# LedOrgan.net
KiCad netlist of a schematic drawn in EAGLE
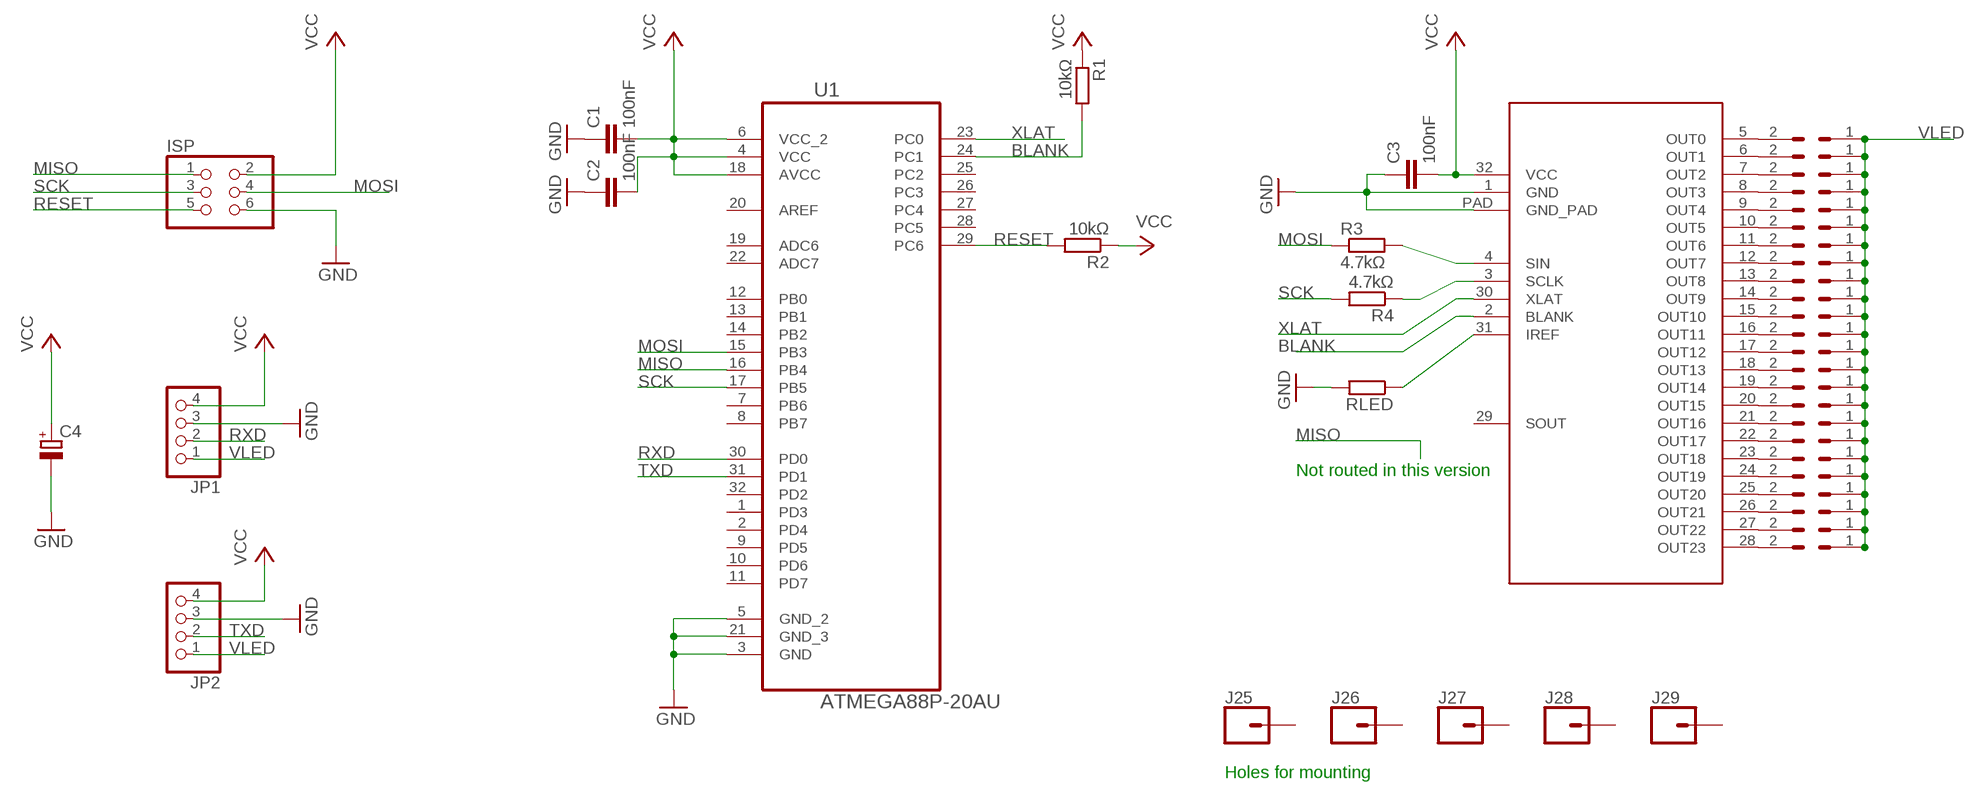
[diagram p0: schematic, sheet 1]

(export (version "E")
  (design (tool "Eeschema 10.0.6"))
  (components
    (comp (ref "C1")
      (value "100nF")
      (footprint "eagle-import:C0402")
      (libsource (lib "eagle-import") (part "C-EUC0402"))
    )
    (comp (ref "C2")
      (value "100nF")
      (footprint "eagle-import:C0402")
      (libsource (lib "eagle-import") (part "C-EUC0402"))
    )
    (comp (ref "C3")
      (value "100nF")
      (footprint "eagle-import:C0402")
      (libsource (lib "eagle-import") (part "C-EUC0402"))
    )
    (comp (ref "C4")
      (value "CPOL-EUE2.5-5")
      (footprint "eagle-import:E2,5-5")
      (libsource (lib "eagle-import") (part "CPOL-EUE2.5-5"))
    )
    (comp (ref "ISP")
      (value "PINHD-2X3")
      (footprint "eagle-import:2X03")
      (libsource (lib "eagle-import") (part "PINHD-2X3"))
    )
    (comp (ref "J1")
      (value "CONN_021X02_NO_SILK")
      (footprint "eagle-import:1X02_NO_SILK")
      (libsource (lib "eagle-import") (part "CONN_021X02_NO_SILK"))
    )
    (comp (ref "J2")
      (value "CONN_021X02_NO_SILK")
      (footprint "eagle-import:1X02_NO_SILK")
      (libsource (lib "eagle-import") (part "CONN_021X02_NO_SILK"))
    )
    (comp (ref "J3")
      (value "CONN_021X02_NO_SILK")
      (footprint "eagle-import:1X02_NO_SILK")
      (libsource (lib "eagle-import") (part "CONN_021X02_NO_SILK"))
    )
    (comp (ref "J4")
      (value "CONN_021X02_NO_SILK")
      (footprint "eagle-import:1X02_NO_SILK")
      (libsource (lib "eagle-import") (part "CONN_021X02_NO_SILK"))
    )
    (comp (ref "J5")
      (value "CONN_021X02_NO_SILK")
      (footprint "eagle-import:1X02_NO_SILK")
      (libsource (lib "eagle-import") (part "CONN_021X02_NO_SILK"))
    )
    (comp (ref "J6")
      (value "CONN_021X02_NO_SILK")
      (footprint "eagle-import:1X02_NO_SILK")
      (libsource (lib "eagle-import") (part "CONN_021X02_NO_SILK"))
    )
    (comp (ref "J7")
      (value "CONN_021X02_NO_SILK")
      (footprint "eagle-import:1X02_NO_SILK")
      (libsource (lib "eagle-import") (part "CONN_021X02_NO_SILK"))
    )
    (comp (ref "J8")
      (value "CONN_021X02_NO_SILK")
      (footprint "eagle-import:1X02_NO_SILK")
      (libsource (lib "eagle-import") (part "CONN_021X02_NO_SILK"))
    )
    (comp (ref "J9")
      (value "CONN_021X02_NO_SILK")
      (footprint "eagle-import:1X02_NO_SILK")
      (libsource (lib "eagle-import") (part "CONN_021X02_NO_SILK"))
    )
    (comp (ref "J10")
      (value "CONN_021X02_NO_SILK")
      (footprint "eagle-import:1X02_NO_SILK")
      (libsource (lib "eagle-import") (part "CONN_021X02_NO_SILK"))
    )
    (comp (ref "J11")
      (value "CONN_021X02_NO_SILK")
      (footprint "eagle-import:1X02_NO_SILK")
      (libsource (lib "eagle-import") (part "CONN_021X02_NO_SILK"))
    )
    (comp (ref "J12")
      (value "CONN_021X02_NO_SILK")
      (footprint "eagle-import:1X02_NO_SILK")
      (libsource (lib "eagle-import") (part "CONN_021X02_NO_SILK"))
    )
    (comp (ref "J13")
      (value "CONN_021X02_NO_SILK")
      (footprint "eagle-import:1X02_NO_SILK")
      (libsource (lib "eagle-import") (part "CONN_021X02_NO_SILK"))
    )
    (comp (ref "J14")
      (value "CONN_021X02_NO_SILK")
      (footprint "eagle-import:1X02_NO_SILK")
      (libsource (lib "eagle-import") (part "CONN_021X02_NO_SILK"))
    )
    (comp (ref "J15")
      (value "CONN_021X02_NO_SILK")
      (footprint "eagle-import:1X02_NO_SILK")
      (libsource (lib "eagle-import") (part "CONN_021X02_NO_SILK"))
    )
    (comp (ref "J16")
      (value "CONN_021X02_NO_SILK")
      (footprint "eagle-import:1X02_NO_SILK")
      (libsource (lib "eagle-import") (part "CONN_021X02_NO_SILK"))
    )
    (comp (ref "J17")
      (value "CONN_021X02_NO_SILK")
      (footprint "eagle-import:1X02_NO_SILK")
      (libsource (lib "eagle-import") (part "CONN_021X02_NO_SILK"))
    )
    (comp (ref "J18")
      (value "CONN_021X02_NO_SILK")
      (footprint "eagle-import:1X02_NO_SILK")
      (libsource (lib "eagle-import") (part "CONN_021X02_NO_SILK"))
    )
    (comp (ref "J19")
      (value "CONN_021X02_NO_SILK")
      (footprint "eagle-import:1X02_NO_SILK")
      (libsource (lib "eagle-import") (part "CONN_021X02_NO_SILK"))
    )
    (comp (ref "J20")
      (value "CONN_021X02_NO_SILK")
      (footprint "eagle-import:1X02_NO_SILK")
      (libsource (lib "eagle-import") (part "CONN_021X02_NO_SILK"))
    )
    (comp (ref "J21")
      (value "CONN_021X02_NO_SILK")
      (footprint "eagle-import:1X02_NO_SILK")
      (libsource (lib "eagle-import") (part "CONN_021X02_NO_SILK"))
    )
    (comp (ref "J22")
      (value "CONN_021X02_NO_SILK")
      (footprint "eagle-import:1X02_NO_SILK")
      (libsource (lib "eagle-import") (part "CONN_021X02_NO_SILK"))
    )
    (comp (ref "J23")
      (value "CONN_021X02_NO_SILK")
      (footprint "eagle-import:1X02_NO_SILK")
      (libsource (lib "eagle-import") (part "CONN_021X02_NO_SILK"))
    )
    (comp (ref "J24")
      (value "CONN_021X02_NO_SILK")
      (footprint "eagle-import:1X02_NO_SILK")
      (libsource (lib "eagle-import") (part "CONN_021X02_NO_SILK"))
    )
    (comp (ref "J25")
      (value "CONN_01PTH_NO_SILK_YES_STOP")
      (footprint "eagle-import:1X01_NO_SILK")
      (libsource (lib "eagle-import") (part "CONN_01PTH_NO_SILK_YES_STOP"))
    )
    (comp (ref "J26")
      (value "CONN_01PTH_NO_SILK_YES_STOP")
      (footprint "eagle-import:1X01_NO_SILK")
      (libsource (lib "eagle-import") (part "CONN_01PTH_NO_SILK_YES_STOP"))
    )
    (comp (ref "J27")
      (value "CONN_01PTH_NO_SILK_YES_STOP")
      (footprint "eagle-import:1X01_NO_SILK")
      (libsource (lib "eagle-import") (part "CONN_01PTH_NO_SILK_YES_STOP"))
    )
    (comp (ref "J28")
      (value "CONN_01PTH_NO_SILK_YES_STOP")
      (footprint "eagle-import:1X01_NO_SILK")
      (libsource (lib "eagle-import") (part "CONN_01PTH_NO_SILK_YES_STOP"))
    )
    (comp (ref "J29")
      (value "CONN_01PTH_NO_SILK_YES_STOP")
      (footprint "eagle-import:1X01_NO_SILK")
      (libsource (lib "eagle-import") (part "CONN_01PTH_NO_SILK_YES_STOP"))
    )
    (comp (ref "JP1")
      (value "PINHD-1X4")
      (footprint "eagle-import:1X04")
      (libsource (lib "eagle-import") (part "PINHD-1X4"))
    )
    (comp (ref "JP2")
      (value "PINHD-1X4")
      (footprint "eagle-import:1X04")
      (libsource (lib "eagle-import") (part "PINHD-1X4"))
    )
    (comp (ref "R1")
      (value "10kΩ")
      (footprint "eagle-import:M0805")
      (libsource (lib "eagle-import") (part "R-EU_M0805"))
    )
    (comp (ref "R2")
      (value "10kΩ")
      (footprint "eagle-import:M0805")
      (libsource (lib "eagle-import") (part "R-EU_M0805"))
    )
    (comp (ref "R3")
      (value "4.7kΩ")
      (footprint "eagle-import:R0402")
      (libsource (lib "eagle-import") (part "R-EU_R0402"))
    )
    (comp (ref "R4")
      (value "4.7kΩ")
      (footprint "eagle-import:R0402")
      (libsource (lib "eagle-import") (part "R-EU_R0402"))
    )
    (comp (ref "RLED")
      (value "R-EU_M0805")
      (footprint "eagle-import:M0805")
      (libsource (lib "eagle-import") (part "R-EU_M0805"))
    )
    (comp (ref "U$2")
      (value "TLC5947")
      (footprint "eagle-import:TSSOP-32")
      (libsource (lib "eagle-import") (part "TLC5947"))
    )
    (comp (ref "U1")
      (value "ATMEGA88P-20AU")
      (footprint "eagle-import:QFP80P900X900X120-32N")
      (libsource (lib "eagle-import") (part "ATMEGA88P-20AU"))
    )
  )
  (nets
    (net (code "1") (name "/BLANK") (class "Default")
      (node (ref "R1") (pin "2") (pinfunction "2_2") (pintype "passive"))
      (node (ref "U$2") (pin "2") (pinfunction "BLANK_2") (pintype "input"))
      (node (ref "U1") (pin "24") (pinfunction "PC1_24") (pintype "bidirectional"))
    )
    (net (code "2") (name "/MISO") (class "Default")
      (node (ref "ISP") (pin "1") (pinfunction "1_1") (pintype "passive"))
      (node (ref "U1") (pin "16") (pinfunction "PB4_16") (pintype "bidirectional"))
    )
    (net (code "3") (name "/MOSI") (class "Default")
      (node (ref "ISP") (pin "4") (pinfunction "4_4") (pintype "passive"))
      (node (ref "R3") (pin "1") (pinfunction "1_1") (pintype "passive"))
      (node (ref "U1") (pin "15") (pinfunction "PB3_15") (pintype "bidirectional"))
    )
    (net (code "4") (name "/RESET") (class "Default")
      (node (ref "ISP") (pin "5") (pinfunction "5_5") (pintype "passive"))
      (node (ref "R2") (pin "2") (pinfunction "2_2") (pintype "passive"))
      (node (ref "U1") (pin "29") (pinfunction "PC6_29") (pintype "bidirectional"))
    )
    (net (code "5") (name "/RXD") (class "Default")
      (node (ref "JP1") (pin "2") (pinfunction "2_2") (pintype "passive"))
      (node (ref "U1") (pin "30") (pinfunction "PD0_30") (pintype "bidirectional"))
    )
    (net (code "6") (name "/SCK") (class "Default")
      (node (ref "ISP") (pin "3") (pinfunction "3_3") (pintype "passive"))
      (node (ref "R4") (pin "2") (pinfunction "2_2") (pintype "passive"))
      (node (ref "U1") (pin "17") (pinfunction "PB5_17") (pintype "bidirectional"))
    )
    (net (code "7") (name "/TXD") (class "Default")
      (node (ref "JP2") (pin "2") (pinfunction "2_2") (pintype "passive"))
      (node (ref "U1") (pin "31") (pinfunction "PD1_31") (pintype "bidirectional"))
    )
    (net (code "8") (name "/VLED") (class "Default")
      (node (ref "J1") (pin "1") (pinfunction "1_1") (pintype "passive"))
      (node (ref "J10") (pin "1") (pinfunction "1_1") (pintype "passive"))
      (node (ref "J11") (pin "1") (pinfunction "1_1") (pintype "passive"))
      (node (ref "J12") (pin "1") (pinfunction "1_1") (pintype "passive"))
      (node (ref "J13") (pin "1") (pinfunction "1_1") (pintype "passive"))
      (node (ref "J14") (pin "1") (pinfunction "1_1") (pintype "passive"))
      (node (ref "J15") (pin "1") (pinfunction "1_1") (pintype "passive"))
      (node (ref "J16") (pin "1") (pinfunction "1_1") (pintype "passive"))
      (node (ref "J17") (pin "1") (pinfunction "1_1") (pintype "passive"))
      (node (ref "J18") (pin "1") (pinfunction "1_1") (pintype "passive"))
      (node (ref "J19") (pin "1") (pinfunction "1_1") (pintype "passive"))
      (node (ref "J2") (pin "1") (pinfunction "1_1") (pintype "passive"))
      (node (ref "J20") (pin "1") (pinfunction "1_1") (pintype "passive"))
      (node (ref "J21") (pin "1") (pinfunction "1_1") (pintype "passive"))
      (node (ref "J22") (pin "1") (pinfunction "1_1") (pintype "passive"))
      (node (ref "J23") (pin "1") (pinfunction "1_1") (pintype "passive"))
      (node (ref "J24") (pin "1") (pinfunction "1_1") (pintype "passive"))
      (node (ref "J3") (pin "1") (pinfunction "1_1") (pintype "passive"))
      (node (ref "J4") (pin "1") (pinfunction "1_1") (pintype "passive"))
      (node (ref "J5") (pin "1") (pinfunction "1_1") (pintype "passive"))
      (node (ref "J6") (pin "1") (pinfunction "1_1") (pintype "passive"))
      (node (ref "J7") (pin "1") (pinfunction "1_1") (pintype "passive"))
      (node (ref "J8") (pin "1") (pinfunction "1_1") (pintype "passive"))
      (node (ref "J9") (pin "1") (pinfunction "1_1") (pintype "passive"))
      (node (ref "JP1") (pin "1") (pinfunction "1_1") (pintype "passive"))
      (node (ref "JP2") (pin "1") (pinfunction "1_1") (pintype "passive"))
    )
    (net (code "9") (name "/XLAT") (class "Default")
      (node (ref "U$2") (pin "30") (pinfunction "XLAT_30") (pintype "input"))
      (node (ref "U1") (pin "23") (pinfunction "PC0_23") (pintype "bidirectional"))
    )
    (net (code "10") (name "GND") (class "Default")
      (node (ref "C1") (pin "1") (pinfunction "1_1") (pintype "passive"))
      (node (ref "C2") (pin "1") (pinfunction "1_1") (pintype "passive"))
      (node (ref "C3") (pin "1") (pinfunction "1_1") (pintype "passive"))
      (node (ref "C4") (pin "-") (pinfunction "-_-") (pintype "passive"))
      (node (ref "ISP") (pin "6") (pinfunction "6_6") (pintype "passive"))
      (node (ref "JP1") (pin "3") (pinfunction "3_3") (pintype "passive"))
      (node (ref "JP2") (pin "3") (pinfunction "3_3") (pintype "passive"))
      (node (ref "RLED") (pin "2") (pinfunction "2_2") (pintype "passive"))
      (node (ref "U$2") (pin "1") (pinfunction "GND_1") (pintype "power_in"))
      (node (ref "U$2") (pin "PAD") (pinfunction "GND_PAD_PAD") (pintype "power_in"))
      (node (ref "U1") (pin "21") (pinfunction "GND_3_21") (pintype "passive"))
      (node (ref "U1") (pin "3") (pinfunction "GND_3") (pintype "passive"))
      (node (ref "U1") (pin "5") (pinfunction "GND_2_5") (pintype "passive"))
    )
    (net (code "11") (name "Net-(U$2-IREF)") (class "Default")
      (node (ref "RLED") (pin "1") (pinfunction "1_1") (pintype "passive"))
      (node (ref "U$2") (pin "31") (pinfunction "IREF_31") (pintype "input"))
    )
    (net (code "12") (name "Net-(U$2-OUT0)") (class "Default")
      (node (ref "J1") (pin "2") (pinfunction "2_2") (pintype "passive"))
      (node (ref "U$2") (pin "5") (pinfunction "OUT0_5") (pintype "bidirectional"))
    )
    (net (code "13") (name "Net-(U$2-OUT1)") (class "Default")
      (node (ref "J2") (pin "2") (pinfunction "2_2") (pintype "passive"))
      (node (ref "U$2") (pin "6") (pinfunction "OUT1_6") (pintype "bidirectional"))
    )
    (net (code "14") (name "Net-(U$2-OUT2)") (class "Default")
      (node (ref "J3") (pin "2") (pinfunction "2_2") (pintype "passive"))
      (node (ref "U$2") (pin "7") (pinfunction "OUT2_7") (pintype "bidirectional"))
    )
    (net (code "15") (name "Net-(U$2-OUT3)") (class "Default")
      (node (ref "J4") (pin "2") (pinfunction "2_2") (pintype "passive"))
      (node (ref "U$2") (pin "8") (pinfunction "OUT3_8") (pintype "bidirectional"))
    )
    (net (code "16") (name "Net-(U$2-OUT4)") (class "Default")
      (node (ref "J5") (pin "2") (pinfunction "2_2") (pintype "passive"))
      (node (ref "U$2") (pin "9") (pinfunction "OUT4_9") (pintype "bidirectional"))
    )
    (net (code "17") (name "Net-(U$2-OUT5)") (class "Default")
      (node (ref "J6") (pin "2") (pinfunction "2_2") (pintype "passive"))
      (node (ref "U$2") (pin "10") (pinfunction "OUT5_10") (pintype "bidirectional"))
    )
    (net (code "18") (name "Net-(U$2-OUT6)") (class "Default")
      (node (ref "J7") (pin "2") (pinfunction "2_2") (pintype "passive"))
      (node (ref "U$2") (pin "11") (pinfunction "OUT6_11") (pintype "bidirectional"))
    )
    (net (code "19") (name "Net-(U$2-OUT7)") (class "Default")
      (node (ref "J8") (pin "2") (pinfunction "2_2") (pintype "passive"))
      (node (ref "U$2") (pin "12") (pinfunction "OUT7_12") (pintype "bidirectional"))
    )
    (net (code "20") (name "Net-(U$2-OUT8)") (class "Default")
      (node (ref "J9") (pin "2") (pinfunction "2_2") (pintype "passive"))
      (node (ref "U$2") (pin "13") (pinfunction "OUT8_13") (pintype "bidirectional"))
    )
    (net (code "21") (name "Net-(U$2-OUT9)") (class "Default")
      (node (ref "J10") (pin "2") (pinfunction "2_2") (pintype "passive"))
      (node (ref "U$2") (pin "14") (pinfunction "OUT9_14") (pintype "bidirectional"))
    )
    (net (code "22") (name "Net-(U$2-OUT10)") (class "Default")
      (node (ref "J11") (pin "2") (pinfunction "2_2") (pintype "passive"))
      (node (ref "U$2") (pin "15") (pinfunction "OUT10_15") (pintype "bidirectional"))
    )
    (net (code "23") (name "Net-(U$2-OUT11)") (class "Default")
      (node (ref "J12") (pin "2") (pinfunction "2_2") (pintype "passive"))
      (node (ref "U$2") (pin "16") (pinfunction "OUT11_16") (pintype "bidirectional"))
    )
    (net (code "24") (name "Net-(U$2-OUT12)") (class "Default")
      (node (ref "J13") (pin "2") (pinfunction "2_2") (pintype "passive"))
      (node (ref "U$2") (pin "17") (pinfunction "OUT12_17") (pintype "bidirectional"))
    )
    (net (code "25") (name "Net-(U$2-OUT13)") (class "Default")
      (node (ref "J14") (pin "2") (pinfunction "2_2") (pintype "passive"))
      (node (ref "U$2") (pin "18") (pinfunction "OUT13_18") (pintype "bidirectional"))
    )
    (net (code "26") (name "Net-(U$2-OUT14)") (class "Default")
      (node (ref "J15") (pin "2") (pinfunction "2_2") (pintype "passive"))
      (node (ref "U$2") (pin "19") (pinfunction "OUT14_19") (pintype "bidirectional"))
    )
    (net (code "27") (name "Net-(U$2-OUT15)") (class "Default")
      (node (ref "J16") (pin "2") (pinfunction "2_2") (pintype "passive"))
      (node (ref "U$2") (pin "20") (pinfunction "OUT15_20") (pintype "bidirectional"))
    )
    (net (code "28") (name "Net-(U$2-OUT16)") (class "Default")
      (node (ref "J17") (pin "2") (pinfunction "2_2") (pintype "passive"))
      (node (ref "U$2") (pin "21") (pinfunction "OUT16_21") (pintype "bidirectional"))
    )
    (net (code "29") (name "Net-(U$2-OUT17)") (class "Default")
      (node (ref "J18") (pin "2") (pinfunction "2_2") (pintype "passive"))
      (node (ref "U$2") (pin "22") (pinfunction "OUT17_22") (pintype "bidirectional"))
    )
    (net (code "30") (name "Net-(U$2-OUT18)") (class "Default")
      (node (ref "J19") (pin "2") (pinfunction "2_2") (pintype "passive"))
      (node (ref "U$2") (pin "23") (pinfunction "OUT18_23") (pintype "bidirectional"))
    )
    (net (code "31") (name "Net-(U$2-OUT19)") (class "Default")
      (node (ref "J20") (pin "2") (pinfunction "2_2") (pintype "passive"))
      (node (ref "U$2") (pin "24") (pinfunction "OUT19_24") (pintype "bidirectional"))
    )
    (net (code "32") (name "Net-(U$2-OUT20)") (class "Default")
      (node (ref "J21") (pin "2") (pinfunction "2_2") (pintype "passive"))
      (node (ref "U$2") (pin "25") (pinfunction "OUT20_25") (pintype "bidirectional"))
    )
    (net (code "33") (name "Net-(U$2-OUT21)") (class "Default")
      (node (ref "J22") (pin "2") (pinfunction "2_2") (pintype "passive"))
      (node (ref "U$2") (pin "26") (pinfunction "OUT21_26") (pintype "bidirectional"))
    )
    (net (code "34") (name "Net-(U$2-OUT22)") (class "Default")
      (node (ref "J23") (pin "2") (pinfunction "2_2") (pintype "passive"))
      (node (ref "U$2") (pin "27") (pinfunction "OUT22_27") (pintype "bidirectional"))
    )
    (net (code "35") (name "Net-(U$2-OUT23)") (class "Default")
      (node (ref "J24") (pin "2") (pinfunction "2_2") (pintype "passive"))
      (node (ref "U$2") (pin "28") (pinfunction "OUT23_28") (pintype "bidirectional"))
    )
    (net (code "36") (name "Net-(U$2-SCLK)") (class "Default")
      (node (ref "R4") (pin "1") (pinfunction "1_1") (pintype "passive"))
      (node (ref "U$2") (pin "3") (pinfunction "SCLK_3") (pintype "input"))
    )
    (net (code "37") (name "Net-(U$2-SIN)") (class "Default")
      (node (ref "R3") (pin "2") (pinfunction "2_2") (pintype "passive"))
      (node (ref "U$2") (pin "4") (pinfunction "SIN_4") (pintype "input"))
    )
    (net (code "38") (name "VCC") (class "Default")
      (node (ref "C1") (pin "2") (pinfunction "2_2") (pintype "passive"))
      (node (ref "C2") (pin "2") (pinfunction "2_2") (pintype "passive"))
      (node (ref "C3") (pin "2") (pinfunction "2_2") (pintype "passive"))
      (node (ref "C4") (pin "+") (pinfunction "+_+") (pintype "passive"))
      (node (ref "ISP") (pin "2") (pinfunction "2_2") (pintype "passive"))
      (node (ref "JP1") (pin "4") (pinfunction "4_4") (pintype "passive"))
      (node (ref "JP2") (pin "4") (pinfunction "4_4") (pintype "passive"))
      (node (ref "R1") (pin "1") (pinfunction "1_1") (pintype "passive"))
      (node (ref "R2") (pin "1") (pinfunction "1_1") (pintype "passive"))
      (node (ref "U$2") (pin "32") (pinfunction "VCC_32") (pintype "power_in"))
      (node (ref "U1") (pin "18") (pinfunction "AVCC_18") (pintype "power_in"))
      (node (ref "U1") (pin "4") (pinfunction "VCC_4") (pintype "power_in"))
      (node (ref "U1") (pin "6") (pinfunction "VCC_2_6") (pintype "power_in"))
    )
    (net (code "39") (name "unconnected-(J25-Pad1)") (class "Default")
      (node (ref "J25") (pin "1") (pinfunction "1_1") (pintype "passive"))
    )
    (net (code "40") (name "unconnected-(J26-Pad1)") (class "Default")
      (node (ref "J26") (pin "1") (pinfunction "1_1") (pintype "passive"))
    )
    (net (code "41") (name "unconnected-(J27-Pad1)") (class "Default")
      (node (ref "J27") (pin "1") (pinfunction "1_1") (pintype "passive"))
    )
    (net (code "42") (name "unconnected-(J28-Pad1)") (class "Default")
      (node (ref "J28") (pin "1") (pinfunction "1_1") (pintype "passive"))
    )
    (net (code "43") (name "unconnected-(J29-Pad1)") (class "Default")
      (node (ref "J29") (pin "1") (pinfunction "1_1") (pintype "passive"))
    )
    (net (code "44") (name "unconnected-(U$2-SOUT-Pad29)") (class "Default")
      (node (ref "U$2") (pin "29") (pinfunction "SOUT_29") (pintype "output"))
    )
    (net (code "45") (name "unconnected-(U1-ADC6-Pad19)") (class "Default")
      (node (ref "U1") (pin "19") (pinfunction "ADC6_19") (pintype "input"))
    )
    (net (code "46") (name "unconnected-(U1-ADC7-Pad22)") (class "Default")
      (node (ref "U1") (pin "22") (pinfunction "ADC7_22") (pintype "input"))
    )
    (net (code "47") (name "unconnected-(U1-AREF-Pad20)") (class "Default")
      (node (ref "U1") (pin "20") (pinfunction "AREF_20") (pintype "input"))
    )
    (net (code "48") (name "unconnected-(U1-PB0-Pad12)") (class "Default")
      (node (ref "U1") (pin "12") (pinfunction "PB0_12") (pintype "bidirectional"))
    )
    (net (code "49") (name "unconnected-(U1-PB1-Pad13)") (class "Default")
      (node (ref "U1") (pin "13") (pinfunction "PB1_13") (pintype "bidirectional"))
    )
    (net (code "50") (name "unconnected-(U1-PB2-Pad14)") (class "Default")
      (node (ref "U1") (pin "14") (pinfunction "PB2_14") (pintype "bidirectional"))
    )
    (net (code "51") (name "unconnected-(U1-PB6-Pad7)") (class "Default")
      (node (ref "U1") (pin "7") (pinfunction "PB6_7") (pintype "bidirectional"))
    )
    (net (code "52") (name "unconnected-(U1-PB7-Pad8)") (class "Default")
      (node (ref "U1") (pin "8") (pinfunction "PB7_8") (pintype "bidirectional"))
    )
    (net (code "53") (name "unconnected-(U1-PC2-Pad25)") (class "Default")
      (node (ref "U1") (pin "25") (pinfunction "PC2_25") (pintype "bidirectional"))
    )
    (net (code "54") (name "unconnected-(U1-PC3-Pad26)") (class "Default")
      (node (ref "U1") (pin "26") (pinfunction "PC3_26") (pintype "bidirectional"))
    )
    (net (code "55") (name "unconnected-(U1-PC4-Pad27)") (class "Default")
      (node (ref "U1") (pin "27") (pinfunction "PC4_27") (pintype "bidirectional"))
    )
    (net (code "56") (name "unconnected-(U1-PC5-Pad28)") (class "Default")
      (node (ref "U1") (pin "28") (pinfunction "PC5_28") (pintype "bidirectional"))
    )
    (net (code "57") (name "unconnected-(U1-PD2-Pad32)") (class "Default")
      (node (ref "U1") (pin "32") (pinfunction "PD2_32") (pintype "bidirectional"))
    )
    (net (code "58") (name "unconnected-(U1-PD3-Pad1)") (class "Default")
      (node (ref "U1") (pin "1") (pinfunction "PD3_1") (pintype "bidirectional"))
    )
    (net (code "59") (name "unconnected-(U1-PD4-Pad2)") (class "Default")
      (node (ref "U1") (pin "2") (pinfunction "PD4_2") (pintype "bidirectional"))
    )
    (net (code "60") (name "unconnected-(U1-PD5-Pad9)") (class "Default")
      (node (ref "U1") (pin "9") (pinfunction "PD5_9") (pintype "bidirectional"))
    )
    (net (code "61") (name "unconnected-(U1-PD6-Pad10)") (class "Default")
      (node (ref "U1") (pin "10") (pinfunction "PD6_10") (pintype "bidirectional"))
    )
    (net (code "62") (name "unconnected-(U1-PD7-Pad11)") (class "Default")
      (node (ref "U1") (pin "11") (pinfunction "PD7_11") (pintype "bidirectional"))
    )
  )
)
